# Reefing-MCU.net
KiCad netlist of a schematic drawn in Altium Designer
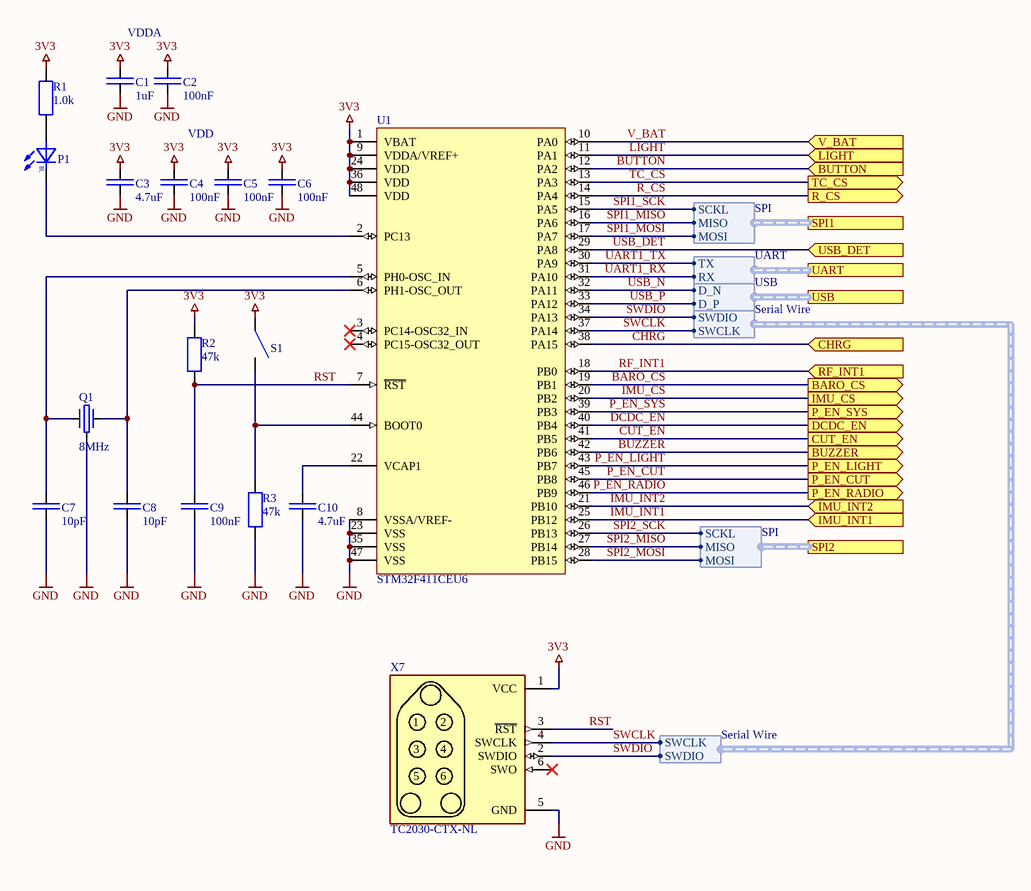
[diagram p0: Reefing-MCU.SchDoc]

(export (version "E")
  (design (tool "Eeschema 10.0.6"))
  (components
    (comp (ref "C1")
      (value "1uF")
      (footprint "SMD Keramikkondensator 0402")
      (description "SMD Ceramic Capacitor E6")
      (libsource (lib "CATS-EUROC") (part "E6 - 1uF"))
    )
    (comp (ref "C2")
      (value "100nF")
      (footprint "SMD Keramikkondensator 0402")
      (description "SMD Ceramic Capacitor E6")
      (libsource (lib "CATS-EUROC") (part "E6 - 100nF"))
    )
    (comp (ref "C3")
      (value "4.7uF")
      (footprint "SMD Keramikkondensator 0402")
      (description "SMD Ceramic Capacitor E6")
      (libsource (lib "CATS-EUROC") (part "E6 - 4.7uF"))
    )
    (comp (ref "C4")
      (value "100nF")
      (footprint "SMD Keramikkondensator 0402")
      (description "SMD Ceramic Capacitor E6")
      (libsource (lib "CATS-EUROC") (part "E6 - 100nF"))
    )
    (comp (ref "C5")
      (value "100nF")
      (footprint "SMD Keramikkondensator 0402")
      (description "SMD Ceramic Capacitor E6")
      (libsource (lib "CATS-EUROC") (part "E6 - 100nF"))
    )
    (comp (ref "C6")
      (value "100nF")
      (footprint "SMD Keramikkondensator 0402")
      (description "SMD Ceramic Capacitor E6")
      (libsource (lib "CATS-EUROC") (part "E6 - 100nF"))
    )
    (comp (ref "C7")
      (value "10pF")
      (footprint "SMD Keramikkondensator 0402")
      (description "SMD Ceramic Capacitor E6")
      (libsource (lib "CATS-EUROC") (part "E6 - 10pF"))
    )
    (comp (ref "C8")
      (value "10pF")
      (footprint "SMD Keramikkondensator 0402")
      (description "SMD Ceramic Capacitor E6")
      (libsource (lib "CATS-EUROC") (part "E6 - 10pF"))
    )
    (comp (ref "C9")
      (value "100nF")
      (footprint "SMD Keramikkondensator 0402")
      (description "SMD Ceramic Capacitor E6")
      (libsource (lib "CATS-EUROC") (part "E6 - 100nF"))
    )
    (comp (ref "C10")
      (value "4.7uF")
      (footprint "SMD Keramikkondensator 0402")
      (description "SMD Ceramic Capacitor E6")
      (libsource (lib "CATS-EUROC") (part "E6 - 4.7uF"))
    )
    (comp (ref "P1")
      (value "LED")
      (footprint "SMD LED 0603")
      (description "Color LED")
      (libsource (lib "Diodes") (part "LED"))
    )
    (comp (ref "Q1")
      (value "8MHz")
      (footprint "SMD Crystal 3.2X2.5X0.8")
      (description "SMD Crystal Resonators 8MHz ±10ppm SMD,3.2x2.5mm")
      (libsource (lib "Other") (part "Crystal"))
    )
    (comp (ref "R1")
      (value "1.0k")
      (footprint "SMD Widerstand 0402")
      (description "SMD Chip Resistor E24")
      (libsource (lib "CATS-EUROC") (part "E24 - 1.0k"))
    )
    (comp (ref "R2")
      (value "47k")
      (footprint "SMD Widerstand 0805")
      (description "SMD Chip Resistor E24")
      (libsource (lib "Resistors-E24") (part "E24 - 47k"))
    )
    (comp (ref "R3")
      (value "47k")
      (footprint "SMD Widerstand 0805")
      (description "SMD Chip Resistor E24")
      (libsource (lib "Resistors-E24") (part "E24 - 47k"))
    )
    (comp (ref "S1")
      (value "SMD-Button")
      (footprint "SMD Button 2.5x3x1.2")
      (description "Button SPST")
      (libsource (lib "CATS-EUROC") (part "Button 3mmx2.5mm"))
    )
    (comp (ref "U1")
      (value "STM32F411CEU6")
      (footprint "SMD IC QFN-48")
      (description "ARM® Cortex®-M4 series Microcontroller IC 32-Bit 100MHz 512KB (512K x 8) FLASH 48-UFQFPN (7x7)")
      (libsource (lib "Microcontrollers") (part "STM32F411CEU6"))
    )
    (comp (ref "X7")
      (value "TC2030-CTX-NL")
      (footprint "SMD Connector TC2030")
      (description "Tag-Connect for ARM-Cortex (6-Pin)")
      (libsource (lib "Connectors") (part "TC2030-CTX-NL"))
    )
  )
  (nets
    (net (code "6") (name "/BARO_CS") (class "Default")
      (node (ref "U1") (pin "19") (pinfunction "PB1_19") (pintype "bidirectional"))
    )
    (net (code "7") (name "/BUTTON") (class "Default")
      (node (ref "U1") (pin "12") (pinfunction "PA2_12") (pintype "bidirectional"))
    )
    (net (code "8") (name "/BUZZER") (class "Default")
      (node (ref "U1") (pin "42") (pinfunction "PB6_42") (pintype "bidirectional"))
    )
    (net (code "9") (name "/CHRG") (class "Default")
      (node (ref "U1") (pin "38") (pinfunction "PA15_38") (pintype "bidirectional"))
    )
    (net (code "10") (name "/CUT_EN") (class "Default")
      (node (ref "U1") (pin "41") (pinfunction "PB5_41") (pintype "bidirectional"))
    )
    (net (code "11") (name "/DCDC_EN") (class "Default")
      (node (ref "U1") (pin "40") (pinfunction "PB4_40") (pintype "bidirectional"))
    )
    (net (code "12") (name "/IMU_CS") (class "Default")
      (node (ref "U1") (pin "20") (pinfunction "PB2_20") (pintype "bidirectional"))
    )
    (net (code "13") (name "/IMU_INT1") (class "Default")
      (node (ref "U1") (pin "25") (pinfunction "PB12_25") (pintype "bidirectional"))
    )
    (net (code "14") (name "/IMU_INT2") (class "Default")
      (node (ref "U1") (pin "21") (pinfunction "PB10_21") (pintype "bidirectional"))
    )
    (net (code "15") (name "/LIGHT") (class "Default")
      (node (ref "U1") (pin "11") (pinfunction "PA1_11") (pintype "bidirectional"))
    )
    (net (code "16") (name "/P_EN_CUT") (class "Default")
      (node (ref "U1") (pin "45") (pinfunction "PB8_45") (pintype "bidirectional"))
    )
    (net (code "17") (name "/P_EN_LIGHT") (class "Default")
      (node (ref "U1") (pin "43") (pinfunction "PB7_43") (pintype "bidirectional"))
    )
    (net (code "18") (name "/P_EN_RADIO") (class "Default")
      (node (ref "U1") (pin "46") (pinfunction "PB9_46") (pintype "bidirectional"))
    )
    (net (code "19") (name "/P_EN_SYS") (class "Default")
      (node (ref "U1") (pin "39") (pinfunction "PB3_39") (pintype "bidirectional"))
    )
    (net (code "20") (name "/RF_INT1") (class "Default")
      (node (ref "U1") (pin "18") (pinfunction "PB0_18") (pintype "bidirectional"))
    )
    (net (code "21") (name "/RST") (class "Default")
      (node (ref "C9") (pin "2") (pinfunction "2_2") (pintype "passive"))
      (node (ref "R2") (pin "1") (pinfunction "1_1") (pintype "passive"))
      (node (ref "U1") (pin "7") (pinfunction "~{RST}_7") (pintype "input"))
      (node (ref "X7") (pin "3") (pinfunction "~{RST}_3") (pintype "output"))
    )
    (net (code "22") (name "/R_CS") (class "Default")
      (node (ref "U1") (pin "14") (pinfunction "PA4_14") (pintype "bidirectional"))
    )
    (net (code "23") (name "/SPI1_MISO") (class "Default")
      (node (ref "U1") (pin "16") (pinfunction "PA6_16") (pintype "bidirectional"))
    )
    (net (code "24") (name "/SPI1_MOSI") (class "Default")
      (node (ref "U1") (pin "17") (pinfunction "PA7_17") (pintype "bidirectional"))
    )
    (net (code "25") (name "/SPI1_SCK") (class "Default")
      (node (ref "U1") (pin "15") (pinfunction "PA5_15") (pintype "bidirectional"))
    )
    (net (code "26") (name "/SPI2_MISO") (class "Default")
      (node (ref "U1") (pin "27") (pinfunction "PB14_27") (pintype "bidirectional"))
    )
    (net (code "27") (name "/SPI2_MOSI") (class "Default")
      (node (ref "U1") (pin "28") (pinfunction "PB15_28") (pintype "bidirectional"))
    )
    (net (code "28") (name "/SPI2_SCK") (class "Default")
      (node (ref "U1") (pin "26") (pinfunction "PB13_26") (pintype "bidirectional"))
    )
    (net (code "29") (name "/SWCLK") (class "Default")
      (node (ref "U1") (pin "37") (pinfunction "PA14_37") (pintype "bidirectional"))
      (node (ref "X7") (pin "4") (pinfunction "SWCLK_4") (pintype "output"))
    )
    (net (code "30") (name "/SWDIO") (class "Default")
      (node (ref "U1") (pin "34") (pinfunction "PA13_34") (pintype "bidirectional"))
      (node (ref "X7") (pin "2") (pinfunction "SWDIO_2") (pintype "bidirectional"))
    )
    (net (code "31") (name "/TC_CS") (class "Default")
      (node (ref "U1") (pin "13") (pinfunction "PA3_13") (pintype "bidirectional"))
    )
    (net (code "32") (name "/UART1_RX") (class "Default")
      (node (ref "U1") (pin "31") (pinfunction "PA10_31") (pintype "bidirectional"))
    )
    (net (code "33") (name "/UART1_TX") (class "Default")
      (node (ref "U1") (pin "30") (pinfunction "PA9_30") (pintype "bidirectional"))
    )
    (net (code "34") (name "/USB_DET") (class "Default")
      (node (ref "U1") (pin "29") (pinfunction "PA8_29") (pintype "bidirectional"))
    )
    (net (code "35") (name "/USB_N") (class "Default")
      (node (ref "U1") (pin "32") (pinfunction "PA11_32") (pintype "bidirectional"))
    )
    (net (code "36") (name "/USB_P") (class "Default")
      (node (ref "U1") (pin "33") (pinfunction "PA12_33") (pintype "bidirectional"))
    )
    (net (code "37") (name "/V_BAT") (class "Default")
      (node (ref "U1") (pin "10") (pinfunction "PA0_10") (pintype "bidirectional"))
    )
    (net (code "42") (name "3V3") (class "Default")
      (node (ref "C1") (pin "2") (pinfunction "2_2") (pintype "passive"))
      (node (ref "C2") (pin "2") (pinfunction "2_2") (pintype "passive"))
      (node (ref "C3") (pin "2") (pinfunction "2_2") (pintype "passive"))
      (node (ref "C4") (pin "2") (pinfunction "2_2") (pintype "passive"))
      (node (ref "C5") (pin "2") (pinfunction "2_2") (pintype "passive"))
      (node (ref "C6") (pin "2") (pinfunction "2_2") (pintype "passive"))
      (node (ref "R1") (pin "2") (pinfunction "2_2") (pintype "passive"))
      (node (ref "R2") (pin "2") (pinfunction "2_2") (pintype "passive"))
      (node (ref "S1") (pin "1") (pinfunction "1_1") (pintype "passive"))
      (node (ref "U1") (pin "1") (pinfunction "VBAT_1") (pintype "passive"))
      (node (ref "U1") (pin "24") (pinfunction "VDD_24") (pintype "passive"))
      (node (ref "U1") (pin "36") (pinfunction "VDD_36") (pintype "passive"))
      (node (ref "U1") (pin "48") (pinfunction "VDD_48") (pintype "passive"))
      (node (ref "U1") (pin "9") (pinfunction "VDDA/VREF+_9") (pintype "passive"))
      (node (ref "X7") (pin "1") (pinfunction "VCC_1") (pintype "power_in"))
    )
    (net (code "43") (name "GND") (class "Default")
      (node (ref "C1") (pin "1") (pinfunction "1_1") (pintype "passive"))
      (node (ref "C10") (pin "1") (pinfunction "1_1") (pintype "passive"))
      (node (ref "C2") (pin "1") (pinfunction "1_1") (pintype "passive"))
      (node (ref "C3") (pin "1") (pinfunction "1_1") (pintype "passive"))
      (node (ref "C4") (pin "1") (pinfunction "1_1") (pintype "passive"))
      (node (ref "C5") (pin "1") (pinfunction "1_1") (pintype "passive"))
      (node (ref "C6") (pin "1") (pinfunction "1_1") (pintype "passive"))
      (node (ref "C7") (pin "1") (pinfunction "1_1") (pintype "passive"))
      (node (ref "C8") (pin "1") (pinfunction "1_1") (pintype "passive"))
      (node (ref "C9") (pin "1") (pinfunction "1_1") (pintype "passive"))
      (node (ref "Q1") (pin "3") (pinfunction "3_3") (pintype "power_in"))
      (node (ref "R3") (pin "1") (pinfunction "1_1") (pintype "passive"))
      (node (ref "U1") (pin "23") (pinfunction "VSS_23") (pintype "passive"))
      (node (ref "U1") (pin "35") (pinfunction "VSS_35") (pintype "passive"))
      (node (ref "U1") (pin "47") (pinfunction "VSS_47") (pintype "passive"))
      (node (ref "U1") (pin "8") (pinfunction "VSSA/VREF-_8") (pintype "passive"))
      (node (ref "X7") (pin "5") (pinfunction "GND_5") (pintype "power_in"))
    )
    (net (code "44") (name "Net-(P1-PadA)") (class "Default")
      (node (ref "P1") (pin "A") (pinfunction "A_A") (pintype "passive"))
      (node (ref "R1") (pin "1") (pinfunction "1_1") (pintype "passive"))
    )
    (net (code "45") (name "Net-(U1-BOOT0)") (class "Default")
      (node (ref "R3") (pin "2") (pinfunction "2_2") (pintype "passive"))
      (node (ref "S1") (pin "2") (pinfunction "2_2") (pintype "passive"))
      (node (ref "U1") (pin "44") (pinfunction "BOOT0_44") (pintype "input"))
    )
    (net (code "46") (name "Net-(U1-PC13)") (class "Default")
      (node (ref "P1") (pin "K") (pinfunction "K_K") (pintype "passive"))
      (node (ref "U1") (pin "2") (pinfunction "PC13_2") (pintype "bidirectional"))
    )
    (net (code "47") (name "Net-(U1-PH0-OSC_IN)") (class "Default")
      (node (ref "C7") (pin "2") (pinfunction "2_2") (pintype "passive"))
      (node (ref "Q1") (pin "1") (pinfunction "1_1") (pintype "passive"))
      (node (ref "U1") (pin "5") (pinfunction "PH0-OSC_IN_5") (pintype "bidirectional"))
    )
    (net (code "48") (name "Net-(U1-PH1-OSC_OUT)") (class "Default")
      (node (ref "C8") (pin "2") (pinfunction "2_2") (pintype "passive"))
      (node (ref "Q1") (pin "2") (pinfunction "2_2") (pintype "passive"))
      (node (ref "U1") (pin "6") (pinfunction "PH1-OSC_OUT_6") (pintype "bidirectional"))
    )
    (net (code "49") (name "Net-(U1-VCAP1)") (class "Default")
      (node (ref "C10") (pin "2") (pinfunction "2_2") (pintype "passive"))
      (node (ref "U1") (pin "22") (pinfunction "VCAP1_22") (pintype "passive"))
    )
    (net (code "50") (name "unconnected-(U1-PC14-OSC32_IN-Pad3)") (class "Default")
      (node (ref "U1") (pin "3") (pinfunction "PC14-OSC32_IN_3") (pintype "bidirectional+no_connect"))
    )
    (net (code "51") (name "unconnected-(U1-PC15-OSC32_OUT-Pad4)") (class "Default")
      (node (ref "U1") (pin "4") (pinfunction "PC15-OSC32_OUT_4") (pintype "bidirectional+no_connect"))
    )
    (net (code "52") (name "unconnected-(X7-SWO-Pad6)") (class "Default")
      (node (ref "X7") (pin "6") (pinfunction "SWO_6") (pintype "input+no_connect"))
    )
  )
)
